# QUTMS-TSAL-V00-S03.net
KiCad netlist of a schematic drawn in Altium Designer
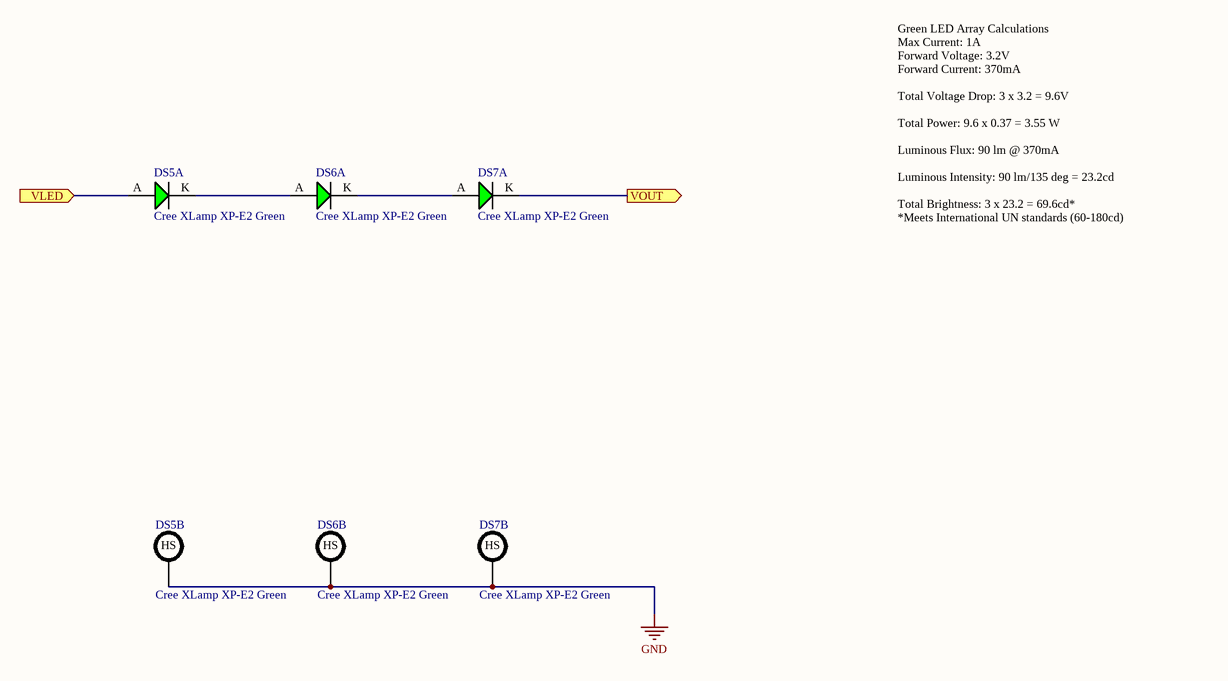
[diagram p0: QUTMS-TSAL-V00-S03.SchDoc]

(export (version "E")
  (design (tool "Eeschema 10.0.6"))
  (components
    (comp (ref "DS5")
      (value "Cree XLamp XP-E2 Green")
      (footprint "Cree XLamp XP-E2")
      (libsource (lib "QUTMS_LEDLibrary") (part "Cree XLamp XP-E2 Green"))
    )
    (comp (ref "DS6")
      (value "Cree XLamp XP-E2 Green")
      (footprint "Cree XLamp XP-E2")
      (libsource (lib "QUTMS_LEDLibrary") (part "Cree XLamp XP-E2 Green"))
    )
    (comp (ref "DS7")
      (value "Cree XLamp XP-E2 Green")
      (footprint "Cree XLamp XP-E2")
      (libsource (lib "QUTMS_LEDLibrary") (part "Cree XLamp XP-E2 Green"))
    )
  )
  (nets
    (net (code "1") (name "/VLED") (class "Default")
      (node (ref "DS5") (pin "A") (pinfunction "A_A") (pintype "passive"))
    )
    (net (code "2") (name "/VOUT") (class "Default")
      (node (ref "DS7") (pin "K") (pinfunction "K_K") (pintype "passive"))
    )
    (net (code "3") (name "GND") (class "Default")
      (node (ref "DS5") (pin "HS") (pinfunction "HS_HS") (pintype "passive"))
      (node (ref "DS6") (pin "HS") (pinfunction "HS_HS") (pintype "passive"))
      (node (ref "DS7") (pin "HS") (pinfunction "HS_HS") (pintype "passive"))
    )
    (net (code "4") (name "Net-(DS5-PadK)") (class "Default")
      (node (ref "DS5") (pin "K") (pinfunction "K_K") (pintype "passive"))
      (node (ref "DS6") (pin "A") (pinfunction "A_A") (pintype "passive"))
    )
    (net (code "5") (name "Net-(DS6-PadK)") (class "Default")
      (node (ref "DS6") (pin "K") (pinfunction "K_K") (pintype "passive"))
      (node (ref "DS7") (pin "A") (pinfunction "A_A") (pintype "passive"))
    )
  )
)
